# test-and-programmer-v1.net
KiCad netlist of a schematic drawn in EAGLE
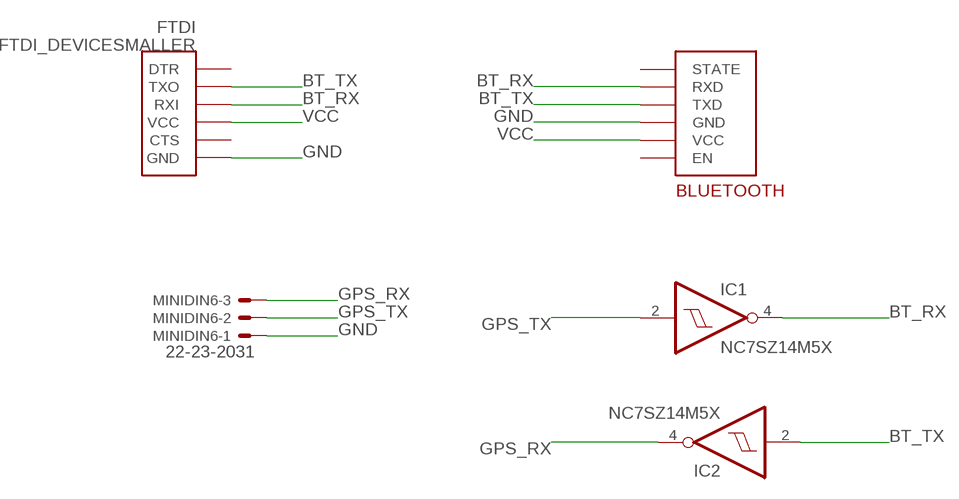
[diagram p0: schematic, sheet 1]

(export (version "E")
  (design (tool "Eeschema 10.0.6"))
  (components
    (comp (ref "BLUETOOTH")
      (value "JY-MCU-BLUETOOTHHORIZONTAL")
      (footprint "eagle-import:JY-MCU-BLUETOOTH-HORIZONTAL")
      (libsource (lib "eagle-import") (part "JY-MCU-BLUETOOTHHORIZONTAL"))
    )
    (comp (ref "FTDI")
      (value "FTDI_DEVICESMALLER")
      (footprint "eagle-import:FTDI_DEVICE_SIDE_SMALLER")
      (libsource (lib "eagle-import") (part "FTDI_DEVICESMALLER"))
    )
    (comp (ref "IC1")
      (value "NC7SZ14M5X")
      (footprint "eagle-import:SOT23-5")
      (libsource (lib "eagle-import") (part "NC7SZ14M5X"))
    )
    (comp (ref "IC2")
      (value "NC7SZ14M5X")
      (footprint "eagle-import:SOT23-5")
      (libsource (lib "eagle-import") (part "NC7SZ14M5X"))
    )
    (comp (ref "MINIDIN6")
      (value "22-23-2031")
      (footprint "eagle-import:22-23-2031")
      (fields (field (name "MF") "MOLEX"))
      (libsource (lib "eagle-import") (part "22-23-2031"))
    )
  )
  (nets
    (net (code "1") (name "/BT_RX") (class "Default")
      (node (ref "BLUETOOTH") (pin "RXD") (pinfunction "RXD_RXD") (pintype "bidirectional"))
      (node (ref "FTDI") (pin "P$3") (pinfunction "RXI_P$3") (pintype "bidirectional"))
      (node (ref "IC1") (pin "4") (pinfunction "O_4") (pintype "output"))
    )
    (net (code "2") (name "/BT_TX") (class "Default")
      (node (ref "BLUETOOTH") (pin "TXD") (pinfunction "TXD_TXD") (pintype "bidirectional"))
      (node (ref "FTDI") (pin "P$2") (pinfunction "TXO_P$2") (pintype "bidirectional"))
      (node (ref "IC2") (pin "2") (pinfunction "I_2") (pintype "input"))
    )
    (net (code "3") (name "/GND") (class "Default")
      (node (ref "BLUETOOTH") (pin "GND") (pinfunction "GND_GND") (pintype "bidirectional"))
      (node (ref "FTDI") (pin "P$6") (pinfunction "GND_P$6") (pintype "bidirectional"))
      (node (ref "MINIDIN6") (pin "1") (pinfunction "S_1") (pintype "passive"))
    )
    (net (code "4") (name "/GPS_RX") (class "Default")
      (node (ref "IC2") (pin "4") (pinfunction "O_4") (pintype "output"))
      (node (ref "MINIDIN6") (pin "3") (pinfunction "S_3") (pintype "passive"))
    )
    (net (code "5") (name "/GPS_TX") (class "Default")
      (node (ref "IC1") (pin "2") (pinfunction "I_2") (pintype "input"))
      (node (ref "MINIDIN6") (pin "2") (pinfunction "S_2") (pintype "passive"))
    )
    (net (code "6") (name "/VCC") (class "Default")
      (node (ref "BLUETOOTH") (pin "VCC") (pinfunction "VCC_VCC") (pintype "bidirectional"))
      (node (ref "FTDI") (pin "P$4") (pinfunction "VCC_P$4") (pintype "bidirectional"))
    )
    (net (code "7") (name "unconnected-(BLUETOOTH-PadEN)") (class "Default")
      (node (ref "BLUETOOTH") (pin "EN") (pinfunction "EN_EN") (pintype "bidirectional"))
    )
    (net (code "8") (name "unconnected-(BLUETOOTH-PadSTATE)") (class "Default")
      (node (ref "BLUETOOTH") (pin "STATE") (pinfunction "STATE_STATE") (pintype "bidirectional"))
    )
    (net (code "9") (name "unconnected-(FTDI-CTS-PadP$5)") (class "Default")
      (node (ref "FTDI") (pin "P$5") (pinfunction "CTS_P$5") (pintype "bidirectional"))
    )
    (net (code "10") (name "unconnected-(FTDI-DTR-PadP$1)") (class "Default")
      (node (ref "FTDI") (pin "P$1") (pinfunction "DTR_P$1") (pintype "bidirectional"))
    )
  )
)
